# Centerboard_-_Prototype_1.net
KiCad netlist of a schematic drawn in EAGLE
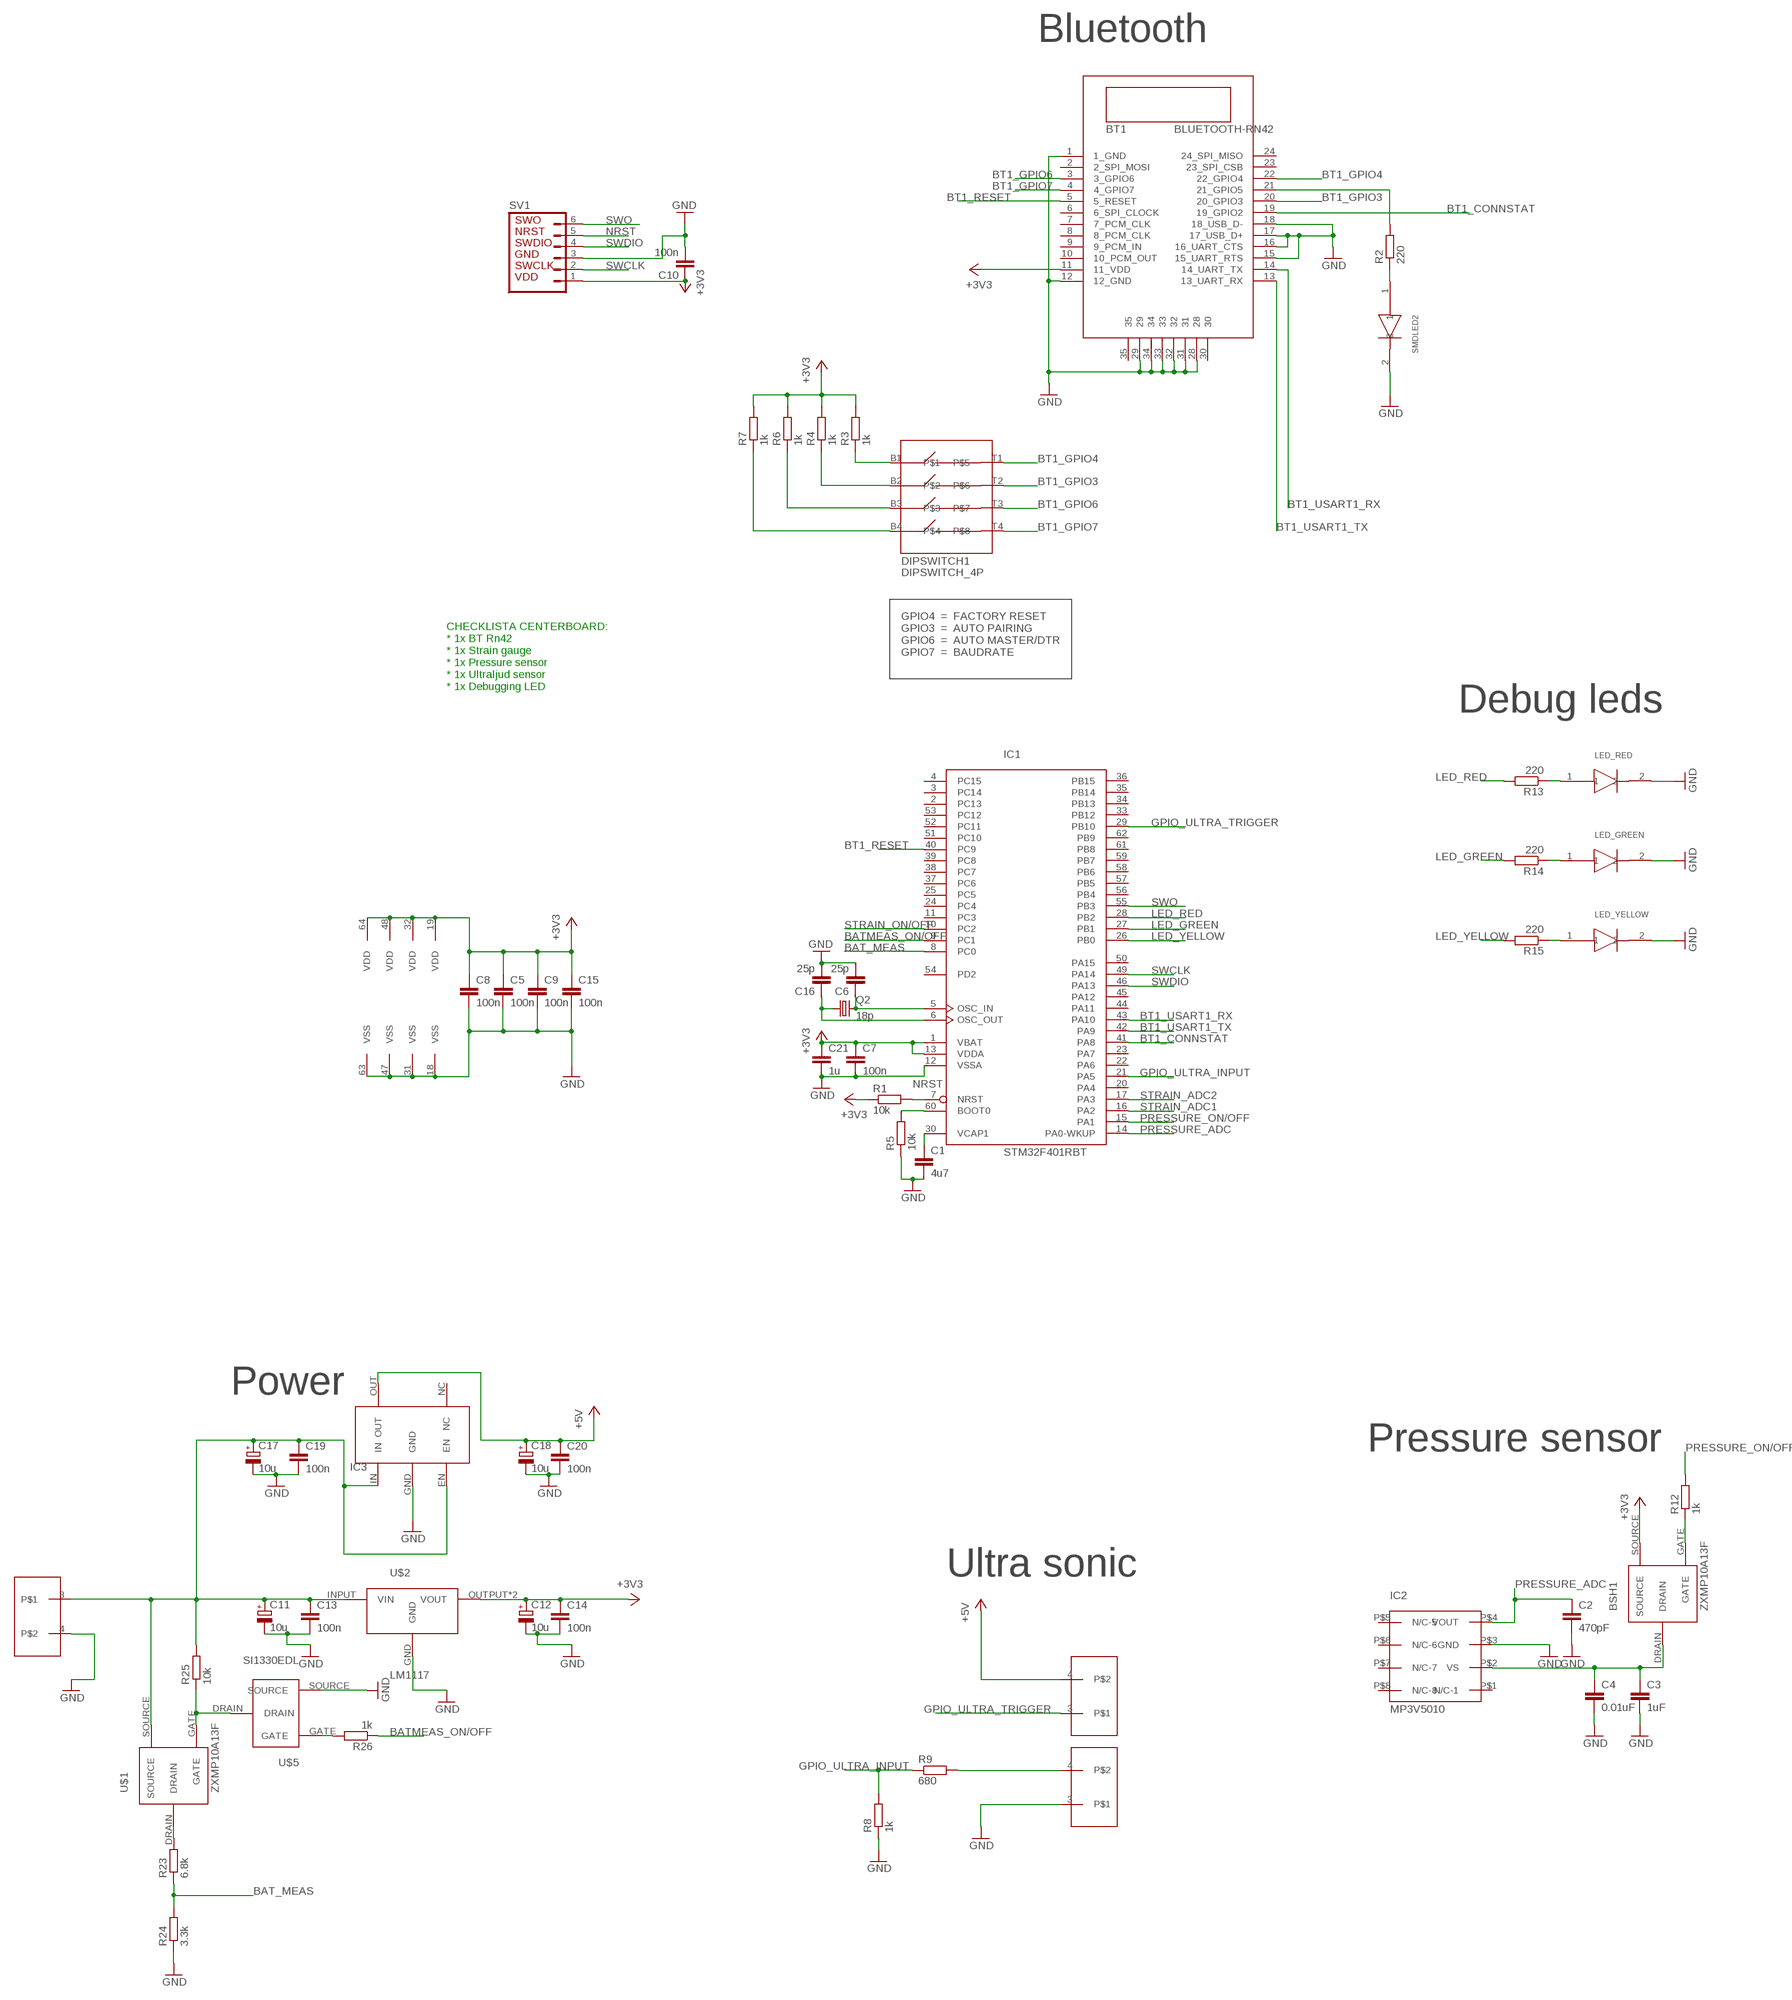
[diagram p0: schematic, sheet 1, part 1 of 2]
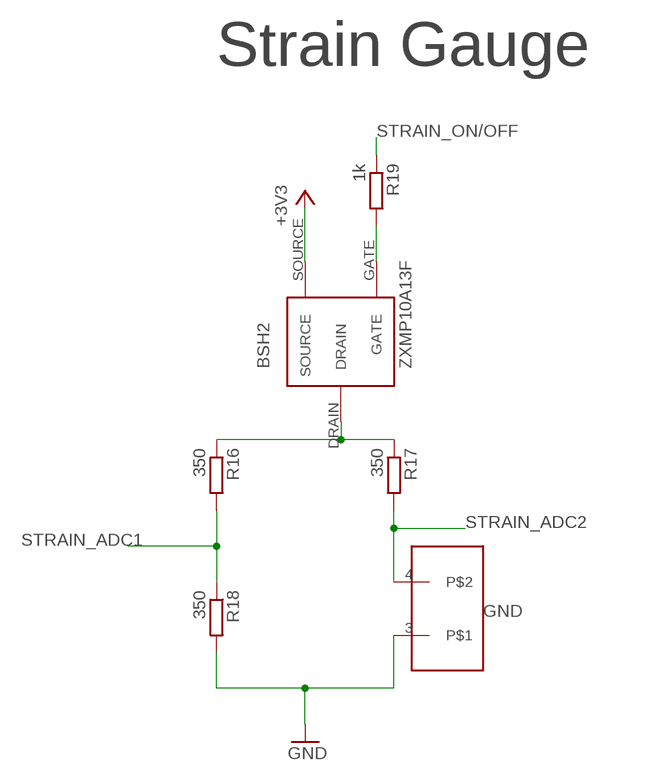
[diagram p1: schematic, sheet 1, part 2 of 2]

(export (version "E")
  (design (tool "Eeschema 10.0.6"))
  (components
    (comp (ref "BSH1")
      (value "ZXMP10A13F")
      (footprint "eagle-import:P-CHANNEL")
      (libsource (lib "eagle-import") (part "ZXMP10A13F"))
    )
    (comp (ref "BSH2")
      (value "ZXMP10A13F")
      (footprint "eagle-import:P-CHANNEL")
      (libsource (lib "eagle-import") (part "ZXMP10A13F"))
    )
    (comp (ref "BT1")
      (value "BLUETOOTH-RN42")
      (footprint "eagle-import:RN42")
      (libsource (lib "eagle-import") (part "BLUETOOTH-RN42"))
    )
    (comp (ref "C1")
      (value "4u7")
      (footprint "eagle-import:C0805")
      (libsource (lib "eagle-import") (part "C-EUC0805"))
    )
    (comp (ref "C2")
      (value "470pF")
      (footprint "eagle-import:C0805")
      (libsource (lib "eagle-import") (part "C-EUC0805"))
    )
    (comp (ref "C3")
      (value "1uF")
      (footprint "eagle-import:C0805")
      (libsource (lib "eagle-import") (part "C-EUC0805"))
    )
    (comp (ref "C4")
      (value "0.01uF")
      (footprint "eagle-import:C0805")
      (libsource (lib "eagle-import") (part "C-EUC0805"))
    )
    (comp (ref "C5")
      (value "100n")
      (footprint "eagle-import:C0805")
      (libsource (lib "eagle-import") (part "C-EUC0805"))
    )
    (comp (ref "C6")
      (value "25p")
      (footprint "eagle-import:C0805")
      (libsource (lib "eagle-import") (part "C-EUC0805"))
    )
    (comp (ref "C7")
      (value "100n")
      (footprint "eagle-import:C0805")
      (libsource (lib "eagle-import") (part "C-EUC0805"))
    )
    (comp (ref "C8")
      (value "100n")
      (footprint "eagle-import:C0805")
      (libsource (lib "eagle-import") (part "C-EUC0805"))
    )
    (comp (ref "C9")
      (value "100n")
      (footprint "eagle-import:C0805")
      (libsource (lib "eagle-import") (part "C-EUC0805"))
    )
    (comp (ref "C10")
      (value "100n")
      (footprint "eagle-import:C0805")
      (libsource (lib "eagle-import") (part "C-EUC0805"))
    )
    (comp (ref "C11")
      (value "10u")
      (footprint "eagle-import:153CLV-0505")
      (libsource (lib "eagle-import") (part "CPOL-EU153CLV-0505"))
    )
    (comp (ref "C12")
      (value "10u")
      (footprint "eagle-import:153CLV-0505")
      (libsource (lib "eagle-import") (part "CPOL-EU153CLV-0505"))
    )
    (comp (ref "C13")
      (value "100n")
      (footprint "eagle-import:C0805")
      (libsource (lib "eagle-import") (part "C-EUC0805"))
    )
    (comp (ref "C14")
      (value "100n")
      (footprint "eagle-import:C0805")
      (libsource (lib "eagle-import") (part "C-EUC0805"))
    )
    (comp (ref "C15")
      (value "100n")
      (footprint "eagle-import:C0805")
      (libsource (lib "eagle-import") (part "C-EUC0805"))
    )
    (comp (ref "C16")
      (value "25p")
      (footprint "eagle-import:C0805")
      (libsource (lib "eagle-import") (part "C-EUC0805"))
    )
    (comp (ref "C17")
      (value "10u")
      (footprint "eagle-import:153CLV-0505")
      (libsource (lib "eagle-import") (part "CPOL-EU153CLV-0505"))
    )
    (comp (ref "C18")
      (value "10u")
      (footprint "eagle-import:153CLV-0505")
      (libsource (lib "eagle-import") (part "CPOL-EU153CLV-0505"))
    )
    (comp (ref "C19")
      (value "100n")
      (footprint "eagle-import:C0805")
      (libsource (lib "eagle-import") (part "C-EUC0805"))
    )
    (comp (ref "C20")
      (value "100n")
      (footprint "eagle-import:C0805")
      (libsource (lib "eagle-import") (part "C-EUC0805"))
    )
    (comp (ref "C21")
      (value "1u")
      (footprint "eagle-import:C0805")
      (libsource (lib "eagle-import") (part "C-EUC0805"))
    )
    (comp (ref "DIPSWITCH1")
      (value "DIPSWITCH_4P")
      (footprint "eagle-import:DIPSWITCH4P")
      (libsource (lib "eagle-import") (part "DIPSWITCH_4P"))
    )
    (comp (ref "IC1")
      (value "STM32F401RBT")
      (footprint "eagle-import:LQFP64")
      (libsource (lib "eagle-import") (part "STM32F401RTB"))
    )
    (comp (ref "IC2")
      (value "MP3V5010")
      (footprint "eagle-import:CASE1351")
      (libsource (lib "eagle-import") (part "MP3V5010"))
    )
    (comp (ref "IC3")
      (value "TPS76150DBVT")
      (footprint "eagle-import:TPS76150DBVT")
      (libsource (lib "eagle-import") (part "TPS76150DBVT"))
    )
    (comp (ref "LED_GREEN")
      (value "SMD_LED")
      (footprint "eagle-import:SMD_LED_CUSTOM")
      (libsource (lib "eagle-import") (part "SMD_LED"))
    )
    (comp (ref "LED_RED")
      (value "SMD_LED")
      (footprint "eagle-import:SMD_LED_CUSTOM")
      (libsource (lib "eagle-import") (part "SMD_LED"))
    )
    (comp (ref "LED_YELLOW")
      (value "SMD_LED")
      (footprint "eagle-import:SMD_LED_CUSTOM")
      (libsource (lib "eagle-import") (part "SMD_LED"))
    )
    (comp (ref "Q2")
      (value "18p")
      (footprint "eagle-import:HC49UP")
      (libsource (lib "eagle-import") (part "CRYSTALHC49UP"))
    )
    (comp (ref "R1")
      (value "10k")
      (footprint "eagle-import:R0805")
      (libsource (lib "eagle-import") (part "R-EU_R0805"))
    )
    (comp (ref "R2")
      (value "220")
      (footprint "eagle-import:R0805")
      (libsource (lib "eagle-import") (part "resistor_R-EU_R0805"))
    )
    (comp (ref "R3")
      (value "1k")
      (footprint "eagle-import:R0805")
      (libsource (lib "eagle-import") (part "resistor_R-EU_R0805"))
    )
    (comp (ref "R4")
      (value "1k")
      (footprint "eagle-import:R0805")
      (libsource (lib "eagle-import") (part "resistor_R-EU_R0805"))
    )
    (comp (ref "R5")
      (value "10k")
      (footprint "eagle-import:R0805")
      (libsource (lib "eagle-import") (part "R-EU_R0805"))
    )
    (comp (ref "R6")
      (value "1k")
      (footprint "eagle-import:R0805")
      (libsource (lib "eagle-import") (part "resistor_R-EU_R0805"))
    )
    (comp (ref "R7")
      (value "1k")
      (footprint "eagle-import:R0805")
      (libsource (lib "eagle-import") (part "resistor_R-EU_R0805"))
    )
    (comp (ref "R8")
      (value "1k")
      (footprint "eagle-import:R0805")
      (libsource (lib "eagle-import") (part "R-EU_R0805"))
    )
    (comp (ref "R9")
      (value "680")
      (footprint "eagle-import:R0805")
      (libsource (lib "eagle-import") (part "R-EU_R0805"))
    )
    (comp (ref "R12")
      (value "1k")
      (footprint "eagle-import:R0805")
      (libsource (lib "eagle-import") (part "R-EU_R0805"))
    )
    (comp (ref "R13")
      (value "220")
      (footprint "eagle-import:R0805")
      (libsource (lib "eagle-import") (part "resistor_R-EU_R0805"))
    )
    (comp (ref "R14")
      (value "220")
      (footprint "eagle-import:R0805")
      (libsource (lib "eagle-import") (part "resistor_R-EU_R0805"))
    )
    (comp (ref "R15")
      (value "220")
      (footprint "eagle-import:R0805")
      (libsource (lib "eagle-import") (part "resistor_R-EU_R0805"))
    )
    (comp (ref "R16")
      (value "350")
      (footprint "eagle-import:R0805")
      (libsource (lib "eagle-import") (part "R-EU_R0805"))
    )
    (comp (ref "R17")
      (value "350")
      (footprint "eagle-import:R0805")
      (libsource (lib "eagle-import") (part "R-EU_R0805"))
    )
    (comp (ref "R18")
      (value "350")
      (footprint "eagle-import:R0805")
      (libsource (lib "eagle-import") (part "R-EU_R0805"))
    )
    (comp (ref "R19")
      (value "1k")
      (footprint "eagle-import:R0805")
      (libsource (lib "eagle-import") (part "R-EU_R0805"))
    )
    (comp (ref "R23")
      (value "6.8k")
      (footprint "eagle-import:R0805")
      (libsource (lib "eagle-import") (part "R-EU_R0805"))
    )
    (comp (ref "R24")
      (value "3.3k")
      (footprint "eagle-import:R0805")
      (libsource (lib "eagle-import") (part "R-EU_R0805"))
    )
    (comp (ref "R25")
      (value "10k")
      (footprint "eagle-import:R0805")
      (libsource (lib "eagle-import") (part "R-EU_R0805"))
    )
    (comp (ref "R26")
      (value "1k")
      (footprint "eagle-import:R0805")
      (libsource (lib "eagle-import") (part "R-EU_R0805"))
    )
    (comp (ref "SKRUVPLINT_2P1")
      (value "SKRUVPLINT_2P")
      (footprint "eagle-import:SKRUVPLINT_2P")
      (libsource (lib "eagle-import") (part "SKRUVPLINT_2P"))
    )
    (comp (ref "SKRUVPLINT_2P2")
      (value "SKRUVPLINT_2P")
      (footprint "eagle-import:SKRUVPLINT_2P")
      (libsource (lib "eagle-import") (part "SKRUVPLINT_2P"))
    )
    (comp (ref "SKRUVPLINT_2P3")
      (value "SKRUVPLINT_2P")
      (footprint "eagle-import:SKRUVPLINT_2P")
      (libsource (lib "eagle-import") (part "SKRUVPLINT_2P"))
    )
    (comp (ref "SKRUVPLINT_2P5")
      (value "SKRUVPLINT_2P")
      (footprint "eagle-import:SKRUVPLINT_2P")
      (libsource (lib "eagle-import") (part "SKRUVPLINT_2P"))
    )
    (comp (ref "SMDLED2")
      (value "SMD_LED")
      (footprint "eagle-import:SMD_LED_CUSTOM")
      (libsource (lib "eagle-import") (part "SMD_LED"))
    )
    (comp (ref "SV1")
      (value "MA06-1")
      (footprint "eagle-import:MA06-1")
      (libsource (lib "eagle-import") (part "MA06-1"))
    )
    (comp (ref "U$1")
      (value "ZXMP10A13F")
      (footprint "eagle-import:P-CHANNEL")
      (libsource (lib "eagle-import") (part "ZXMP10A13F"))
    )
    (comp (ref "U$2")
      (value "LM1117")
      (footprint "eagle-import:SOT-223")
      (libsource (lib "eagle-import") (part "LM1117"))
    )
    (comp (ref "U$5")
      (value "SI1330EDL")
      (footprint "eagle-import:SOT-323")
      (libsource (lib "eagle-import") (part "SI1330EDL"))
    )
  )
  (nets
    (net (code "1") (name "+3V3") (class "Default")
      (node (ref "BSH1") (pin "SOURCE") (pinfunction "SOURCE_SOURCE") (pintype "bidirectional"))
      (node (ref "BSH2") (pin "SOURCE") (pinfunction "SOURCE_SOURCE") (pintype "bidirectional"))
      (node (ref "BT1") (pin "11") (pinfunction "11_VDD_11") (pintype "bidirectional"))
      (node (ref "C10") (pin "1") (pinfunction "1_1") (pintype "passive"))
      (node (ref "C12") (pin "+") (pinfunction "+_+") (pintype "passive"))
      (node (ref "C14") (pin "1") (pinfunction "1_1") (pintype "passive"))
      (node (ref "C15") (pin "1") (pinfunction "1_1") (pintype "passive"))
      (node (ref "C21") (pin "1") (pinfunction "1_1") (pintype "passive"))
      (node (ref "C5") (pin "1") (pinfunction "1_1") (pintype "passive"))
      (node (ref "C7") (pin "1") (pinfunction "1_1") (pintype "passive"))
      (node (ref "C8") (pin "1") (pinfunction "1_1") (pintype "passive"))
      (node (ref "C9") (pin "1") (pinfunction "1_1") (pintype "passive"))
      (node (ref "IC1") (pin "1") (pinfunction "VBAT_1") (pintype "power_in"))
      (node (ref "IC1") (pin "13") (pinfunction "VDDA_13") (pintype "power_in"))
      (node (ref "IC1") (pin "19") (pinfunction "VDD_19") (pintype "power_in"))
      (node (ref "IC1") (pin "32") (pinfunction "VDD_32") (pintype "power_in"))
      (node (ref "IC1") (pin "48") (pinfunction "VDD_48") (pintype "power_in"))
      (node (ref "IC1") (pin "64") (pinfunction "VDD_64") (pintype "power_in"))
      (node (ref "R1") (pin "1") (pinfunction "1_1") (pintype "passive"))
      (node (ref "R3") (pin "2") (pinfunction "2_2") (pintype "passive"))
      (node (ref "R4") (pin "2") (pinfunction "2_2") (pintype "passive"))
      (node (ref "R6") (pin "2") (pinfunction "2_2") (pintype "passive"))
      (node (ref "R7") (pin "2") (pinfunction "2_2") (pintype "passive"))
      (node (ref "SV1") (pin "1") (pinfunction "1_1") (pintype "passive"))
      (node (ref "U$2") (pin "OUTPUT") (pinfunction "VOUT_OUTPUT") (pintype "bidirectional"))
      (node (ref "U$2") (pin "VOUT") (pinfunction "VOUT_VOUT") (pintype "bidirectional"))
    )
    (net (code "2") (name "+5V") (class "Default")
      (node (ref "C18") (pin "+") (pinfunction "+_+") (pintype "passive"))
      (node (ref "C20") (pin "1") (pinfunction "1_1") (pintype "passive"))
      (node (ref "IC3") (pin "OUT") (pinfunction "OUT_OUT") (pintype "bidirectional"))
      (node (ref "SKRUVPLINT_2P1") (pin "4") (pinfunction "P$2_4") (pintype "bidirectional"))
    )
    (net (code "3") (name "/BATMEAS_ON{slash}OFF") (class "Default")
      (node (ref "IC1") (pin "9") (pinfunction "PC1_9") (pintype "bidirectional"))
      (node (ref "R26") (pin "1") (pinfunction "1_1") (pintype "passive"))
    )
    (net (code "4") (name "/BAT_MEAS") (class "Default")
      (node (ref "IC1") (pin "8") (pinfunction "PC0_8") (pintype "bidirectional"))
      (node (ref "R23") (pin "1") (pinfunction "1_1") (pintype "passive"))
      (node (ref "R24") (pin "2") (pinfunction "2_2") (pintype "passive"))
    )
    (net (code "5") (name "/BT1_CONNSTAT") (class "Default")
      (node (ref "BT1") (pin "19") (pinfunction "19_GPIO2_19") (pintype "bidirectional"))
      (node (ref "IC1") (pin "41") (pinfunction "PA8_41") (pintype "bidirectional"))
    )
    (net (code "6") (name "/BT1_GPIO3") (class "Default")
      (node (ref "BT1") (pin "20") (pinfunction "20_GPIO3_20") (pintype "bidirectional"))
      (node (ref "DIPSWITCH1") (pin "T2") (pinfunction "P$6_T2") (pintype "bidirectional"))
    )
    (net (code "7") (name "/BT1_GPIO4") (class "Default")
      (node (ref "BT1") (pin "22") (pinfunction "22_GPIO4_22") (pintype "bidirectional"))
      (node (ref "DIPSWITCH1") (pin "T1") (pinfunction "P$5_T1") (pintype "bidirectional"))
    )
    (net (code "8") (name "/BT1_GPIO6") (class "Default")
      (node (ref "BT1") (pin "3") (pinfunction "3_GPIO6_3") (pintype "bidirectional"))
      (node (ref "DIPSWITCH1") (pin "T3") (pinfunction "P$7_T3") (pintype "bidirectional"))
    )
    (net (code "9") (name "/BT1_GPIO7") (class "Default")
      (node (ref "BT1") (pin "4") (pinfunction "4_GPIO7_4") (pintype "bidirectional"))
      (node (ref "DIPSWITCH1") (pin "T4") (pinfunction "P$8_T4") (pintype "bidirectional"))
    )
    (net (code "10") (name "/BT1_RESET") (class "Default")
      (node (ref "BT1") (pin "5") (pinfunction "5_RESET_5") (pintype "bidirectional"))
      (node (ref "IC1") (pin "40") (pinfunction "PC9_40") (pintype "bidirectional"))
    )
    (net (code "11") (name "/BT1_USART1_RX") (class "Default")
      (node (ref "BT1") (pin "14") (pinfunction "14_UART_TX_14") (pintype "bidirectional"))
      (node (ref "IC1") (pin "43") (pinfunction "PA10_43") (pintype "bidirectional"))
    )
    (net (code "12") (name "/BT1_USART1_TX") (class "Default")
      (node (ref "BT1") (pin "13") (pinfunction "13_UART_RX_13") (pintype "bidirectional"))
      (node (ref "IC1") (pin "42") (pinfunction "PA9_42") (pintype "bidirectional"))
    )
    (net (code "13") (name "/GPIO_ULTRA_INPUT") (class "Default")
      (node (ref "IC1") (pin "21") (pinfunction "PA5_21") (pintype "bidirectional"))
      (node (ref "R8") (pin "2") (pinfunction "2_2") (pintype "passive"))
      (node (ref "R9") (pin "1") (pinfunction "1_1") (pintype "passive"))
    )
    (net (code "14") (name "/GPIO_ULTRA_TRIGGER") (class "Default")
      (node (ref "IC1") (pin "29") (pinfunction "PB10_29") (pintype "bidirectional"))
      (node (ref "SKRUVPLINT_2P1") (pin "3") (pinfunction "P$1_3") (pintype "bidirectional"))
    )
    (net (code "15") (name "/LED_GREEN") (class "Default")
      (node (ref "IC1") (pin "27") (pinfunction "PB1_27") (pintype "bidirectional"))
      (node (ref "R14") (pin "2") (pinfunction "2_2") (pintype "passive"))
    )
    (net (code "16") (name "/LED_RED") (class "Default")
      (node (ref "IC1") (pin "28") (pinfunction "PB2_28") (pintype "bidirectional"))
      (node (ref "R13") (pin "2") (pinfunction "2_2") (pintype "passive"))
    )
    (net (code "17") (name "/LED_YELLOW") (class "Default")
      (node (ref "IC1") (pin "26") (pinfunction "PB0_26") (pintype "bidirectional"))
      (node (ref "R15") (pin "2") (pinfunction "2_2") (pintype "passive"))
    )
    (net (code "18") (name "/NRST") (class "Default")
      (node (ref "IC1") (pin "7") (pinfunction "NRST_7") (pintype "bidirectional"))
      (node (ref "R1") (pin "2") (pinfunction "2_2") (pintype "passive"))
      (node (ref "SV1") (pin "5") (pinfunction "5_5") (pintype "passive"))
    )
    (net (code "19") (name "/PRESSURE_ADC") (class "Default")
      (node (ref "C2") (pin "1") (pinfunction "1_1") (pintype "passive"))
      (node (ref "IC1") (pin "14") (pinfunction "PA0-WKUP_14") (pintype "bidirectional"))
      (node (ref "IC2") (pin "P$4") (pinfunction "VOUT_P$4") (pintype "bidirectional"))
    )
    (net (code "20") (name "/PRESSURE_ON{slash}OFF") (class "Default")
      (node (ref "IC1") (pin "15") (pinfunction "PA1_15") (pintype "bidirectional"))
      (node (ref "R12") (pin "2") (pinfunction "2_2") (pintype "passive"))
    )
    (net (code "21") (name "/STRAIN_ADC1") (class "Default")
      (node (ref "IC1") (pin "16") (pinfunction "PA2_16") (pintype "bidirectional"))
      (node (ref "R16") (pin "2") (pinfunction "2_2") (pintype "passive"))
      (node (ref "R18") (pin "1") (pinfunction "1_1") (pintype "passive"))
    )
    (net (code "22") (name "/STRAIN_ADC2") (class "Default")
      (node (ref "IC1") (pin "17") (pinfunction "PA3_17") (pintype "bidirectional"))
      (node (ref "R17") (pin "2") (pinfunction "2_2") (pintype "passive"))
      (node (ref "SKRUVPLINT_2P3") (pin "4") (pinfunction "P$2_4") (pintype "bidirectional"))
    )
    (net (code "23") (name "/STRAIN_ON{slash}OFF") (class "Default")
      (node (ref "IC1") (pin "10") (pinfunction "PC2_10") (pintype "bidirectional"))
      (node (ref "R19") (pin "1") (pinfunction "1_1") (pintype "passive"))
    )
    (net (code "24") (name "/SWCLK") (class "Default")
      (node (ref "IC1") (pin "49") (pinfunction "PA14_49") (pintype "bidirectional"))
      (node (ref "SV1") (pin "2") (pinfunction "2_2") (pintype "passive"))
    )
    (net (code "25") (name "/SWDIO") (class "Default")
      (node (ref "IC1") (pin "46") (pinfunction "PA13_46") (pintype "bidirectional"))
      (node (ref "SV1") (pin "4") (pinfunction "4_4") (pintype "passive"))
    )
    (net (code "26") (name "/SWO") (class "Default")
      (node (ref "IC1") (pin "55") (pinfunction "PB3_55") (pintype "bidirectional"))
      (node (ref "SV1") (pin "6") (pinfunction "6_6") (pintype "passive"))
    )
    (net (code "27") (name "GND") (class "Default")
      (node (ref "BT1") (pin "1") (pinfunction "1_GND_1") (pintype "bidirectional"))
      (node (ref "BT1") (pin "12") (pinfunction "12_GND_12") (pintype "bidirectional"))
      (node (ref "BT1") (pin "15") (pinfunction "15_UART_RTS_15") (pintype "bidirectional"))
      (node (ref "BT1") (pin "16") (pinfunction "16_UART_CTS_16") (pintype "bidirectional"))
      (node (ref "BT1") (pin "17") (pinfunction "17_USB_D+_17") (pintype "bidirectional"))
      (node (ref "BT1") (pin "18") (pinfunction "18_USB_D-_18") (pintype "bidirectional"))
      (node (ref "BT1") (pin "28") (pinfunction "28_28") (pintype "bidirectional"))
      (node (ref "BT1") (pin "29") (pinfunction "29_29") (pintype "bidirectional"))
      (node (ref "BT1") (pin "31") (pinfunction "31_31") (pintype "bidirectional"))
      (node (ref "BT1") (pin "32") (pinfunction "32_32") (pintype "bidirectional"))
      (node (ref "BT1") (pin "33") (pinfunction "33_33") (pintype "bidirectional"))
      (node (ref "BT1") (pin "34") (pinfunction "34_34") (pintype "bidirectional"))
      (node (ref "C1") (pin "2") (pinfunction "2_2") (pintype "passive"))
      (node (ref "C10") (pin "2") (pinfunction "2_2") (pintype "passive"))
      (node (ref "C11") (pin "-") (pinfunction "-_-") (pintype "passive"))
      (node (ref "C12") (pin "-") (pinfunction "-_-") (pintype "passive"))
      (node (ref "C13") (pin "2") (pinfunction "2_2") (pintype "passive"))
      (node (ref "C14") (pin "2") (pinfunction "2_2") (pintype "passive"))
      (node (ref "C15") (pin "2") (pinfunction "2_2") (pintype "passive"))
      (node (ref "C16") (pin "2") (pinfunction "2_2") (pintype "passive"))
      (node (ref "C17") (pin "-") (pinfunction "-_-") (pintype "passive"))
      (node (ref "C18") (pin "-") (pinfunction "-_-") (pintype "passive"))
      (node (ref "C19") (pin "2") (pinfunction "2_2") (pintype "passive"))
      (node (ref "C2") (pin "2") (pinfunction "2_2") (pintype "passive"))
      (node (ref "C20") (pin "2") (pinfunction "2_2") (pintype "passive"))
      (node (ref "C21") (pin "2") (pinfunction "2_2") (pintype "passive"))
      (node (ref "C3") (pin "2") (pinfunction "2_2") (pintype "passive"))
      (node (ref "C4") (pin "2") (pinfunction "2_2") (pintype "passive"))
      (node (ref "C5") (pin "2") (pinfunction "2_2") (pintype "passive"))
      (node (ref "C6") (pin "2") (pinfunction "2_2") (pintype "passive"))
      (node (ref "C7") (pin "2") (pinfunction "2_2") (pintype "passive"))
      (node (ref "C8") (pin "2") (pinfunction "2_2") (pintype "passive"))
      (node (ref "C9") (pin "2") (pinfunction "2_2") (pintype "passive"))
      (node (ref "IC1") (pin "12") (pinfunction "VSSA_12") (pintype "power_in"))
      (node (ref "IC1") (pin "18") (pinfunction "VSS_18") (pintype "power_in"))
      (node (ref "IC1") (pin "31") (pinfunction "VSS_31") (pintype "power_in"))
      (node (ref "IC1") (pin "47") (pinfunction "VSS_47") (pintype "power_in"))
      (node (ref "IC1") (pin "63") (pinfunction "VSS_63") (pintype "power_in"))
      (node (ref "IC2") (pin "P$3") (pinfunction "GND_P$3") (pintype "bidirectional"))
      (node (ref "IC3") (pin "GND") (pinfunction "GND_GND") (pintype "bidirectional"))
      (node (ref "LED_GREEN") (pin "2") (pinfunction "2_2") (pintype "bidirectional"))
      (node (ref "LED_RED") (pin "2") (pinfunction "2_2") (pintype "bidirectional"))
      (node (ref "LED_YELLOW") (pin "2") (pinfunction "2_2") (pintype "bidirectional"))
      (node (ref "R18") (pin "2") (pinfunction "2_2") (pintype "passive"))
      (node (ref "R24") (pin "1") (pinfunction "1_1") (pintype "passive"))
      (node (ref "R5") (pin "1") (pinfunction "1_1") (pintype "passive"))
      (node (ref "R8") (pin "1") (pinfunction "1_1") (pintype "passive"))
      (node (ref "SKRUVPLINT_2P2") (pin "3") (pinfunction "P$1_3") (pintype "bidirectional"))
      (node (ref "SKRUVPLINT_2P3") (pin "3") (pinfunction "P$1_3") (pintype "bidirectional"))
      (node (ref "SKRUVPLINT_2P5") (pin "4") (pinfunction "P$2_4") (pintype "bidirectional"))
      (node (ref "SMDLED2") (pin "2") (pinfunction "2_2") (pintype "bidirectional"))
      (node (ref "SV1") (pin "3") (pinfunction "3_3") (pintype "passive"))
      (node (ref "U$2") (pin "GND") (pinfunction "GND_GND") (pintype "bidirectional"))
      (node (ref "U$5") (pin "SOURCE") (pinfunction "SOURCE_SOURCE") (pintype "bidirectional"))
    )
    (net (code "28") (name "Net-(BSH1-PadGATE)") (class "Default")
      (node (ref "BSH1") (pin "GATE") (pinfunction "GATE_GATE") (pintype "bidirectional"))
      (node (ref "R12") (pin "1") (pinfunction "1_1") (pintype "passive"))
    )
    (net (code "29") (name "Net-(BSH2-PadDRAIN)") (class "Default")
      (node (ref "BSH2") (pin "DRAIN") (pinfunction "DRAIN_DRAIN") (pintype "bidirectional"))
      (node (ref "R16") (pin "1") (pinfunction "1_1") (pintype "passive"))
      (node (ref "R17") (pin "1") (pinfunction "1_1") (pintype "passive"))
    )
    (net (code "30") (name "Net-(BSH2-PadGATE)") (class "Default")
      (node (ref "BSH2") (pin "GATE") (pinfunction "GATE_GATE") (pintype "bidirectional"))
      (node (ref "R19") (pin "2") (pinfunction "2_2") (pintype "passive"))
    )
    (net (code "31") (name "Net-(BT1-21_GPIO5)") (class "Default")
      (node (ref "BT1") (pin "21") (pinfunction "21_GPIO5_21") (pintype "bidirectional"))
      (node (ref "R2") (pin "2") (pinfunction "2_2") (pintype "passive"))
    )
    (net (code "32") (name "Net-(DIPSWITCH1-P$1)") (class "Default")
      (node (ref "DIPSWITCH1") (pin "B1") (pinfunction "P$1_B1") (pintype "bidirectional"))
      (node (ref "R3") (pin "1") (pinfunction "1_1") (pintype "passive"))
    )
    (net (code "33") (name "Net-(DIPSWITCH1-P$2)") (class "Default")
      (node (ref "DIPSWITCH1") (pin "B2") (pinfunction "P$2_B2") (pintype "bidirectional"))
      (node (ref "R4") (pin "1") (pinfunction "1_1") (pintype "passive"))
    )
    (net (code "34") (name "Net-(DIPSWITCH1-P$3)") (class "Default")
      (node (ref "DIPSWITCH1") (pin "B3") (pinfunction "P$3_B3") (pintype "bidirectional"))
      (node (ref "R6") (pin "1") (pinfunction "1_1") (pintype "passive"))
    )
    (net (code "35") (name "Net-(DIPSWITCH1-P$4)") (class "Default")
      (node (ref "DIPSWITCH1") (pin "B4") (pinfunction "P$4_B4") (pintype "bidirectional"))
      (node (ref "R7") (pin "1") (pinfunction "1_1") (pintype "passive"))
    )
    (net (code "36") (name "Net-(IC1A-BOOT0)") (class "Default")
      (node (ref "IC1") (pin "60") (pinfunction "BOOT0_60") (pintype "input"))
      (node (ref "R5") (pin "2") (pinfunction "2_2") (pintype "passive"))
    )
    (net (code "37") (name "Net-(IC1A-OSC_IN)") (class "Default")
      (node (ref "C6") (pin "1") (pinfunction "1_1") (pintype "passive"))
      (node (ref "IC1") (pin "5") (pinfunction "OSC_IN_5") (pintype "bidirectional"))
      (node (ref "Q2") (pin "2") (pinfunction "2_2") (pintype "passive"))
    )
    (net (code "38") (name "Net-(IC1A-OSC_OUT)") (class "Default")
      (node (ref "C16") (pin "1") (pinfunction "1_1") (pintype "passive"))
      (node (ref "IC1") (pin "6") (pinfunction "OSC_OUT_6") (pintype "bidirectional"))
      (node (ref "Q2") (pin "1") (pinfunction "1_1") (pintype "passive"))
    )
    (net (code "39") (name "Net-(IC1A-VCAP1)") (class "Default")
      (node (ref "C1") (pin "1") (pinfunction "1_1") (pintype "passive"))
      (node (ref "IC1") (pin "30") (pinfunction "VCAP1_30") (pintype "power_in"))
    )
    (net (code "40") (name "Net-(IC2-VS)") (class "Default")
      (node (ref "BSH1") (pin "DRAIN") (pinfunction "DRAIN_DRAIN") (pintype "bidirectional"))
      (node (ref "C3") (pin "1") (pinfunction "1_1") (pintype "passive"))
      (node (ref "C4") (pin "1") (pinfunction "1_1") (pintype "passive"))
      (node (ref "IC2") (pin "P$2") (pinfunction "VS_P$2") (pintype "bidirectional"))
    )
    (net (code "41") (name "Net-(LED_GREEN-Pad1)") (class "Default")
      (node (ref "LED_GREEN") (pin "1") (pinfunction "1_1") (pintype "bidirectional"))
      (node (ref "R14") (pin "1") (pinfunction "1_1") (pintype "passive"))
    )
    (net (code "42") (name "Net-(LED_RED-Pad1)") (class "Default")
      (node (ref "LED_RED") (pin "1") (pinfunction "1_1") (pintype "bidirectional"))
      (node (ref "R13") (pin "1") (pinfunction "1_1") (pintype "passive"))
    )
    (net (code "43") (name "Net-(LED_YELLOW-Pad1)") (class "Default")
      (node (ref "LED_YELLOW") (pin "1") (pinfunction "1_1") (pintype "bidirectional"))
      (node (ref "R15") (pin "1") (pinfunction "1_1") (pintype "passive"))
    )
    (net (code "44") (name "Net-(R2-Pad1)") (class "Default")
      (node (ref "R2") (pin "1") (pinfunction "1_1") (pintype "passive"))
      (node (ref "SMDLED2") (pin "1") (pinfunction "1_1") (pintype "bidirectional"))
    )
    (net (code "45") (name "Net-(R23-Pad2)") (class "Default")
      (node (ref "R23") (pin "2") (pinfunction "2_2") (pintype "passive"))
      (node (ref "U$1") (pin "DRAIN") (pinfunction "DRAIN_DRAIN") (pintype "bidirectional"))
    )
    (net (code "46") (name "Net-(R25-Pad1)") (class "Default")
      (node (ref "R25") (pin "1") (pinfunction "1_1") (pintype "passive"))
      (node (ref "U$1") (pin "GATE") (pinfunction "GATE_GATE") (pintype "bidirectional"))
      (node (ref "U$5") (pin "DRAIN") (pinfunction "DRAIN_DRAIN") (pintype "bidirectional"))
    )
    (net (code "47") (name "Net-(R26-Pad2)") (class "Default")
      (node (ref "R26") (pin "2") (pinfunction "2_2") (pintype "passive"))
      (node (ref "U$5") (pin "GATE") (pinfunction "GATE_GATE") (pintype "bidirectional"))
    )
    (net (code "48") (name "Net-(SKRUVPLINT_2P2-P$2)") (class "Default")
      (node (ref "R9") (pin "2") (pinfunction "2_2") (pintype "passive"))
      (node (ref "SKRUVPLINT_2P2") (pin "4") (pinfunction "P$2_4") (pintype "bidirectional"))
    )
    (net (code "49") (name "Net-(SKRUVPLINT_2P5-P$1)") (class "Default")
      (node (ref "C11") (pin "+") (pinfunction "+_+") (pintype "passive"))
      (node (ref "C13") (pin "1") (pinfunction "1_1") (pintype "passive"))
      (node (ref "C17") (pin "+") (pinfunction "+_+") (pintype "passive"))
      (node (ref "C19") (pin "1") (pinfunction "1_1") (pintype "passive"))
      (node (ref "IC3") (pin "EN") (pinfunction "EN_EN") (pintype "bidirectional"))
      (node (ref "IC3") (pin "IN") (pinfunction "IN_IN") (pintype "bidirectional"))
      (node (ref "R25") (pin "2") (pinfunction "2_2") (pintype "passive"))
      (node (ref "SKRUVPLINT_2P5") (pin "3") (pinfunction "P$1_3") (pintype "bidirectional"))
      (node (ref "U$1") (pin "SOURCE") (pinfunction "SOURCE_SOURCE") (pintype "bidirectional"))
      (node (ref "U$2") (pin "INPUT") (pinfunction "VIN_INPUT") (pintype "bidirectional"))
    )
    (net (code "50") (name "unconnected-(BT1-2_SPI_MOSI-Pad2)") (class "Default")
      (node (ref "BT1") (pin "2") (pinfunction "2_SPI_MOSI_2") (pintype "bidirectional"))
    )
    (net (code "51") (name "unconnected-(BT1-6_SPI_CLOCK-Pad6)") (class "Default")
      (node (ref "BT1") (pin "6") (pinfunction "6_SPI_CLOCK_6") (pintype "bidirectional"))
    )
    (net (code "52") (name "unconnected-(BT1-7_PCM_CLK-Pad7)") (class "Default")
      (node (ref "BT1") (pin "7") (pinfunction "7_PCM_CLK_7") (pintype "bidirectional"))
    )
    (net (code "53") (name "unconnected-(BT1-8_PCM_CLK-Pad8)") (class "Default")
      (node (ref "BT1") (pin "8") (pinfunction "8_PCM_CLK_8") (pintype "bidirectional"))
    )
    (net (code "54") (name "unconnected-(BT1-9_PCM_IN-Pad9)") (class "Default")
      (node (ref "BT1") (pin "9") (pinfunction "9_PCM_IN_9") (pintype "bidirectional"))
    )
    (net (code "55") (name "unconnected-(BT1-10_PCM_OUT-Pad10)") (class "Default")
      (node (ref "BT1") (pin "10") (pinfunction "10_PCM_OUT_10") (pintype "bidirectional"))
    )
    (net (code "56") (name "unconnected-(BT1-23_SPI_CSB-Pad23)") (class "Default")
      (node (ref "BT1") (pin "23") (pinfunction "23_SPI_CSB_23") (pintype "bidirectional"))
    )
    (net (code "57") (name "unconnected-(BT1-24_SPI_MISO-Pad24)") (class "Default")
      (node (ref "BT1") (pin "24") (pinfunction "24_SPI_MISO_24") (pintype "bidirectional"))
    )
    (net (code "58") (name "unconnected-(BT1-Pad30)") (class "Default")
      (node (ref "BT1") (pin "30") (pinfunction "30_30") (pintype "bidirectional"))
    )
    (net (code "59") (name "unconnected-(BT1-Pad35)") (class "Default")
      (node (ref "BT1") (pin "35") (pinfunction "35_35") (pintype "bidirectional"))
    )
    (net (code "60") (name "unconnected-(IC1A-PA4-Pad20)") (class "Default")
      (node (ref "IC1") (pin "20") (pinfunction "PA4_20") (pintype "bidirectional"))
    )
    (net (code "61") (name "unconnected-(IC1A-PA6-Pad22)") (class "Default")
      (node (ref "IC1") (pin "22") (pinfunction "PA6_22") (pintype "bidirectional"))
    )
    (net (code "62") (name "unconnected-(IC1A-PA7-Pad23)") (class "Default")
      (node (ref "IC1") (pin "23") (pinfunction "PA7_23") (pintype "bidirectional"))
    )
    (net (code "63") (name "unconnected-(IC1A-PA11-Pad44)") (class "Default")
      (node (ref "IC1") (pin "44") (pinfunction "PA11_44") (pintype "bidirectional"))
    )
    (net (code "64") (name "unconnected-(IC1A-PA12-Pad45)") (class "Default")
      (node (ref "IC1") (pin "45") (pinfunction "PA12_45") (pintype "bidirectional"))
    )
    (net (code "65") (name "unconnected-(IC1A-PA15-Pad50)") (class "Default")
      (node (ref "IC1") (pin "50") (pinfunction "PA15_50") (pintype "bidirectional"))
    )
    (net (code "66") (name "unconnected-(IC1A-PB4-Pad56)") (class "Default")
      (node (ref "IC1") (pin "56") (pinfunction "PB4_56") (pintype "bidirectional"))
    )
    (net (code "67") (name "unconnected-(IC1A-PB5-Pad57)") (class "Default")
      (node (ref "IC1") (pin "57") (pinfunction "PB5_57") (pintype "bidirectional"))
    )
    (net (code "68") (name "unconnected-(IC1A-PB6-Pad58)") (class "Default")
      (node (ref "IC1") (pin "58") (pinfunction "PB6_58") (pintype "bidirectional"))
    )
    (net (code "69") (name "unconnected-(IC1A-PB7-Pad59)") (class "Default")
      (node (ref "IC1") (pin "59") (pinfunction "PB7_59") (pintype "bidirectional"))
    )
    (net (code "70") (name "unconnected-(IC1A-PB8-Pad61)") (class "Default")
      (node (ref "IC1") (pin "61") (pinfunction "PB8_61") (pintype "bidirectional"))
    )
    (net (code "71") (name "unconnected-(IC1A-PB9-Pad62)") (class "Default")
      (node (ref "IC1") (pin "62") (pinfunction "PB9_62") (pintype "bidirectional"))
    )
    (net (code "72") (name "unconnected-(IC1A-PB12-Pad33)") (class "Default")
      (node (ref "IC1") (pin "33") (pinfunction "PB12_33") (pintype "bidirectional"))
    )
    (net (code "73") (name "unconnected-(IC1A-PB13-Pad34)") (class "Default")
      (node (ref "IC1") (pin "34") (pinfunction "PB13_34") (pintype "bidirectional"))
    )
    (net (code "74") (name "unconnected-(IC1A-PB14-Pad35)") (class "Default")
      (node (ref "IC1") (pin "35") (pinfunction "PB14_35") (pintype "bidirectional"))
    )
    (net (code "75") (name "unconnected-(IC1A-PB15-Pad36)") (class "Default")
      (node (ref "IC1") (pin "36") (pinfunction "PB15_36") (pintype "bidirectional"))
    )
    (net (code "76") (name "unconnected-(IC1A-PC3-Pad11)") (class "Default")
      (node (ref "IC1") (pin "11") (pinfunction "PC3_11") (pintype "bidirectional"))
    )
    (net (code "77") (name "unconnected-(IC1A-PC4-Pad24)") (class "Default")
      (node (ref "IC1") (pin "24") (pinfunction "PC4_24") (pintype "bidirectional"))
    )
    (net (code "78") (name "unconnected-(IC1A-PC5-Pad25)") (class "Default")
      (node (ref "IC1") (pin "25") (pinfunction "PC5_25") (pintype "bidirectional"))
    )
    (net (code "79") (name "unconnected-(IC1A-PC6-Pad37)") (class "Default")
      (node (ref "IC1") (pin "37") (pinfunction "PC6_37") (pintype "bidirectional"))
    )
    (net (code "80") (name "unconnected-(IC1A-PC7-Pad38)") (class "Default")
      (node (ref "IC1") (pin "38") (pinfunction "PC7_38") (pintype "bidirectional"))
    )
    (net (code "81") (name "unconnected-(IC1A-PC8-Pad39)") (class "Default")
      (node (ref "IC1") (pin "39") (pinfunction "PC8_39") (pintype "bidirectional"))
    )
    (net (code "82") (name "unconnected-(IC1A-PC10-Pad51)") (class "Default")
      (node (ref "IC1") (pin "51") (pinfunction "PC10_51") (pintype "bidirectional"))
    )
    (net (code "83") (name "unconnected-(IC1A-PC11-Pad52)") (class "Default")
      (node (ref "IC1") (pin "52") (pinfunction "PC11_52") (pintype "bidirectional"))
    )
    (net (code "84") (name "unconnected-(IC1A-PC12-Pad53)") (class "Default")
      (node (ref "IC1") (pin "53") (pinfunction "PC12_53") (pintype "bidirectional"))
    )
    (net (code "85") (name "unconnected-(IC1A-PC13-Pad2)") (class "Default")
      (node (ref "IC1") (pin "2") (pinfunction "PC13_2") (pintype "bidirectional"))
    )
    (net (code "86") (name "unconnected-(IC1A-PC14-Pad3)") (class "Default")
      (node (ref "IC1") (pin "3") (pinfunction "PC14_3") (pintype "bidirectional"))
    )
    (net (code "87") (name "unconnected-(IC1A-PC15-Pad4)") (class "Default")
      (node (ref "IC1") (pin "4") (pinfunction "PC15_4") (pintype "bidirectional"))
    )
    (net (code "88") (name "unconnected-(IC1A-PD2-Pad54)") (class "Default")
      (node (ref "IC1") (pin "54") (pinfunction "PD2_54") (pintype "bidirectional"))
    )
    (net (code "89") (name "unconnected-(IC2-N{slash}C-1-PadP$1)") (class "Default")
      (node (ref "IC2") (pin "P$1") (pinfunction "N/C-1_P$1") (pintype "bidirectional"))
    )
    (net (code "90") (name "unconnected-(IC2-N{slash}C-5-PadP$5)") (class "Default")
      (node (ref "IC2") (pin "P$5") (pinfunction "N/C-5_P$5") (pintype "bidirectional"))
    )
    (net (code "91") (name "unconnected-(IC2-N{slash}C-6-PadP$6)") (class "Default")
      (node (ref "IC2") (pin "P$6") (pinfunction "N/C-6_P$6") (pintype "bidirectional"))
    )
    (net (code "92") (name "unconnected-(IC2-N{slash}C-7-PadP$7)") (class "Default")
      (node (ref "IC2") (pin "P$7") (pinfunction "N/C-7_P$7") (pintype "bidirectional"))
    )
    (net (code "93") (name "unconnected-(IC2-N{slash}C-8-PadP$8)") (class "Default")
      (node (ref "IC2") (pin "P$8") (pinfunction "N/C-8_P$8") (pintype "bidirectional"))
    )
    (net (code "94") (name "unconnected-(IC3-PadNC)") (class "Default")
      (node (ref "IC3") (pin "NC") (pinfunction "NC_NC") (pintype "bidirectional"))
    )
  )
)
